# ProProject___2024-10-02.net
KiCad netlist of a schematic drawn in EasyEDA Pro
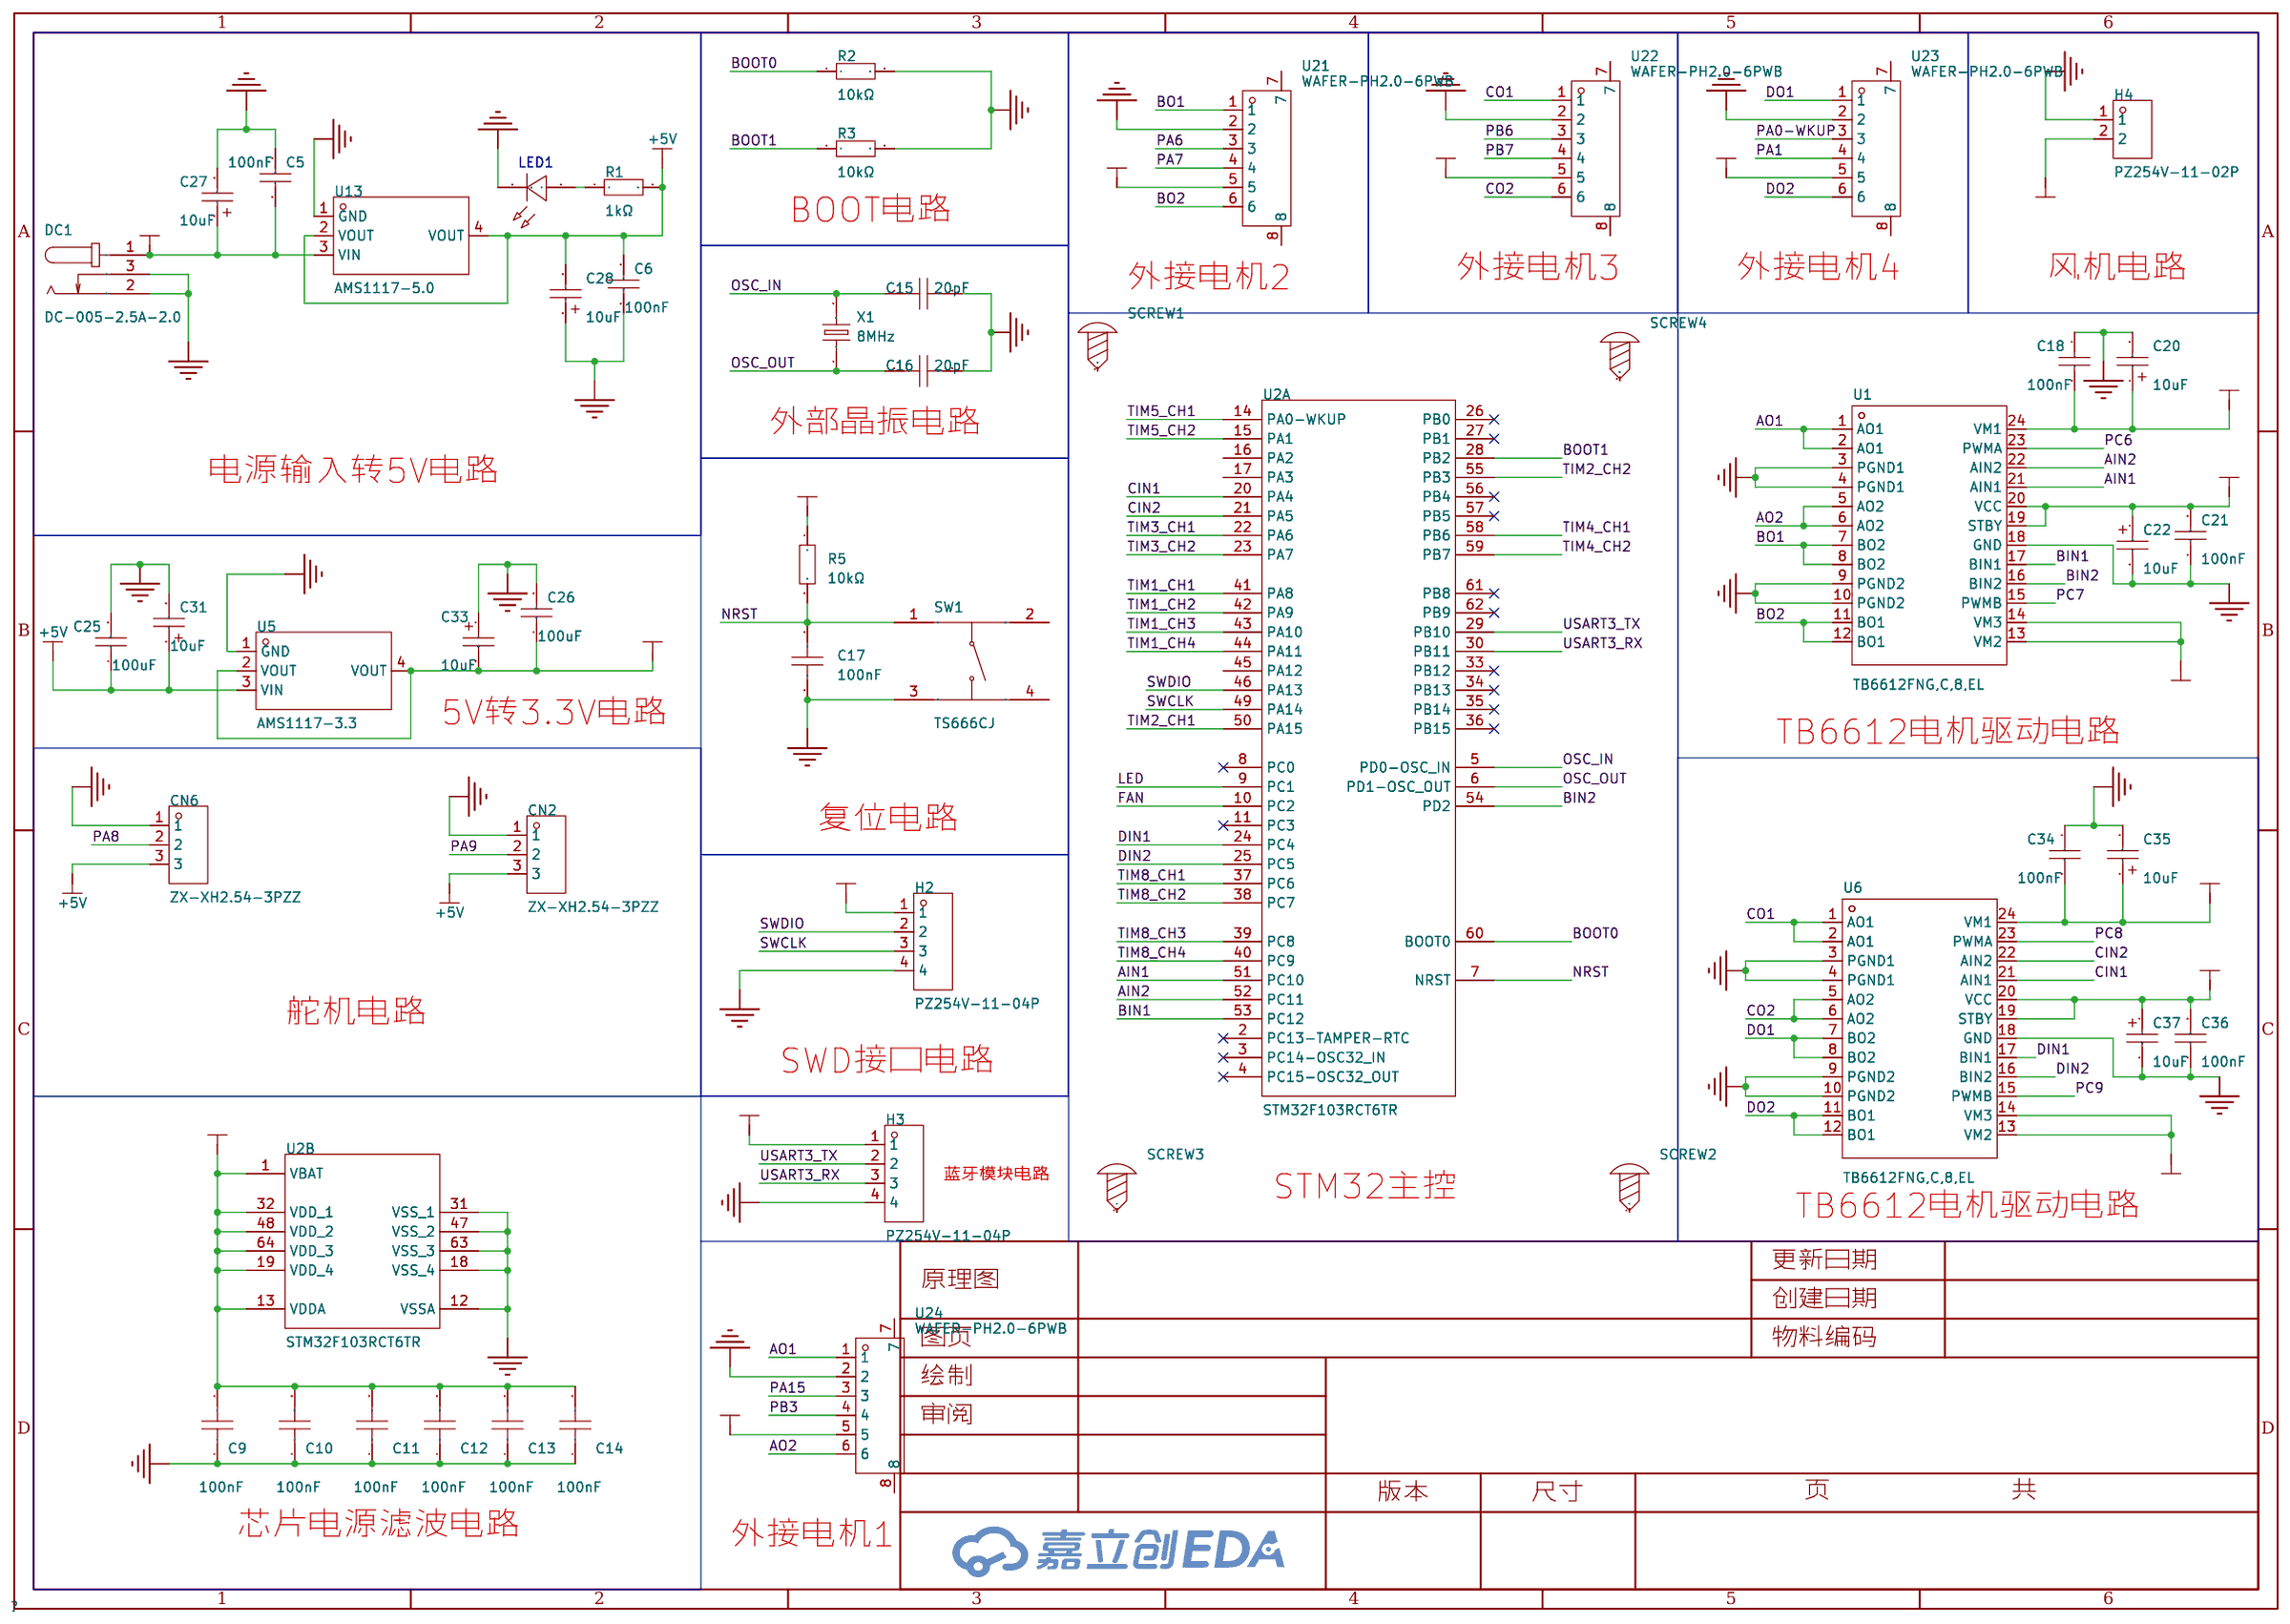
[diagram p0: schematic sheet]

(export (version "E")
  (design (tool "Eeschema 10.0.6"))
  (components
    (comp (ref "C5")
      (value "100nF")
      (footprint "easyedapro:C0805")
      (description "容值:100nF;精度:±10%;额定电压:50V;材质(温度系数):X7R;")
      (fields
        (field (name "Manufacturer Part") "CC0805KRX7R9BB104")
        (field (name "Manufacturer") "YAGEO(国巨)")
      )
      (libsource (lib "easyedapro") (part "CC0805KRX7R9BB104"))
    )
    (comp (ref "C6")
      (value "100nF")
      (footprint "easyedapro:C0805")
      (description "容值:100nF;精度:±10%;额定电压:50V;材质(温度系数):X7R;")
      (fields
        (field (name "Manufacturer Part") "CC0805KRX7R9BB104")
        (field (name "Manufacturer") "YAGEO(国巨)")
      )
      (libsource (lib "easyedapro") (part "CC0805KRX7R9BB104"))
    )
    (comp (ref "C9")
      (value "100nF")
      (footprint "easyedapro:C0603")
      (description "容值:100nF;精度:±10%;额定电压:50V;材质(温度系数):X7R;")
      (fields
        (field (name "Manufacturer Part") "CC0603KRX7R9BB104")
        (field (name "Manufacturer") "YAGEO(国巨)")
      )
      (libsource (lib "easyedapro") (part "CC0603KRX7R9BB104"))
    )
    (comp (ref "C10")
      (value "100nF")
      (footprint "easyedapro:C0603")
      (description "容值:100nF;精度:±10%;额定电压:50V;材质(温度系数):X7R;")
      (fields
        (field (name "Manufacturer Part") "CC0603KRX7R9BB104")
        (field (name "Manufacturer") "YAGEO(国巨)")
      )
      (libsource (lib "easyedapro") (part "CC0603KRX7R9BB104"))
    )
    (comp (ref "C11")
      (value "100nF")
      (footprint "easyedapro:C0603")
      (description "容值:100nF;精度:±10%;额定电压:50V;材质(温度系数):X7R;")
      (fields
        (field (name "Manufacturer Part") "CC0603KRX7R9BB104")
        (field (name "Manufacturer") "YAGEO(国巨)")
      )
      (libsource (lib "easyedapro") (part "CC0603KRX7R9BB104"))
    )
    (comp (ref "C12")
      (value "100nF")
      (footprint "easyedapro:C0603")
      (description "容值:100nF;精度:±10%;额定电压:50V;材质(温度系数):X7R;")
      (fields
        (field (name "Manufacturer Part") "CC0603KRX7R9BB104")
        (field (name "Manufacturer") "YAGEO(国巨)")
      )
      (libsource (lib "easyedapro") (part "CC0603KRX7R9BB104"))
    )
    (comp (ref "C13")
      (value "100nF")
      (footprint "easyedapro:C0603")
      (description "容值:100nF;精度:±10%;额定电压:50V;材质(温度系数):X7R;")
      (fields
        (field (name "Manufacturer Part") "CC0603KRX7R9BB104")
        (field (name "Manufacturer") "YAGEO(国巨)")
      )
      (libsource (lib "easyedapro") (part "CC0603KRX7R9BB104"))
    )
    (comp (ref "C14")
      (value "100nF")
      (footprint "easyedapro:C0603")
      (description "容值:100nF;精度:±10%;额定电压:50V;材质(温度系数):X7R;")
      (fields
        (field (name "Manufacturer Part") "CC0603KRX7R9BB104")
        (field (name "Manufacturer") "YAGEO(国巨)")
      )
      (libsource (lib "easyedapro") (part "CC0603KRX7R9BB104"))
    )
    (comp (ref "C15")
      (value "20pF")
      (footprint "easyedapro:C0805")
      (description "容值:20pF;精度:±5%;额定电压:50V;材质(温度系数):C0G;")
      (fields (field (name "Manufacturer Part") "0805CG200J500NT") (field (name "Manufacturer") "FH(风华)"))
      (libsource (lib "easyedapro") (part "0805CG200J500NT"))
    )
    (comp (ref "C16")
      (value "20pF")
      (footprint "easyedapro:C0805")
      (description "容值:20pF;精度:±5%;额定电压:50V;材质(温度系数):C0G;")
      (fields (field (name "Manufacturer Part") "0805CG200J500NT") (field (name "Manufacturer") "FH(风华)"))
      (libsource (lib "easyedapro") (part "0805CG200J500NT"))
    )
    (comp (ref "C17")
      (value "100nF")
      (footprint "easyedapro:C0603")
      (description "容值:100nF;精度:±10%;额定电压:50V;材质(温度系数):X7R;")
      (fields
        (field (name "Manufacturer Part") "CC0603KRX7R9BB104")
        (field (name "Manufacturer") "YAGEO(国巨)")
      )
      (libsource (lib "easyedapro") (part "CC0603KRX7R9BB104"))
    )
    (comp (ref "C18")
      (value "100nF")
      (footprint "easyedapro:C0805")
      (description "容值:100nF;精度:±10%;额定电压:50V;材质(温度系数):X7R;")
      (fields
        (field (name "Manufacturer Part") "CC0805KRX7R9BB104")
        (field (name "Manufacturer") "YAGEO(国巨)")
      )
      (libsource (lib "easyedapro") (part "CC0805KRX7R9BB104"))
    )
    (comp (ref "C20")
      (value "10uF")
      (footprint "easyedapro:CAP-SMD_L3.2-W1.6-RD-C7171")
      (description "容值:10uF;精度:±10%;额定电压:16V;等效串联电阻:3Ω@100kHz;")
      (fields (field (name "Manufacturer Part") "TAJA106K016RNJ") (field (name "Manufacturer") "Kyocera AVX"))
      (libsource (lib "easyedapro") (part "TAJA106K016RNJ"))
    )
    (comp (ref "C21")
      (value "100nF")
      (footprint "easyedapro:C0805")
      (description "容值:100nF;精度:±10%;额定电压:50V;材质(温度系数):X7R;")
      (fields
        (field (name "Manufacturer Part") "CC0805KRX7R9BB104")
        (field (name "Manufacturer") "YAGEO(国巨)")
      )
      (libsource (lib "easyedapro") (part "CC0805KRX7R9BB104"))
    )
    (comp (ref "C22")
      (value "10uF")
      (footprint "easyedapro:CAP-SMD_L3.2-W1.6-RD-C7171")
      (description "容值:10uF;精度:±10%;额定电压:16V;等效串联电阻:3Ω@100kHz;")
      (fields (field (name "Manufacturer Part") "TAJA106K016RNJ") (field (name "Manufacturer") "Kyocera AVX"))
      (libsource (lib "easyedapro") (part "TAJA106K016RNJ"))
    )
    (comp (ref "C25")
      (value "100uF")
      (footprint "easyedapro:C0805")
      (description "容值:100uF;精度:±20%;额定电压:6.3V;材质(温度系数):X5R;")
      (fields
        (field (name "Manufacturer Part") "GRM21BR60J107ME15L")
        (field (name "Manufacturer") "muRata(村田)")
      )
      (libsource (lib "easyedapro") (part "GRM21BR60J107ME15L"))
    )
    (comp (ref "C26")
      (value "100uF")
      (footprint "easyedapro:C0805")
      (description "容值:100uF;精度:±20%;额定电压:6.3V;材质(温度系数):X5R;")
      (fields
        (field (name "Manufacturer Part") "GRM21BR60J107ME15L")
        (field (name "Manufacturer") "muRata(村田)")
      )
      (libsource (lib "easyedapro") (part "GRM21BR60J107ME15L"))
    )
    (comp (ref "C27")
      (value "10uF")
      (footprint "easyedapro:CAP-SMD_L3.2-W1.6-RD-C7171")
      (description "容值:10uF;精度:±10%;额定电压:16V;等效串联电阻:3Ω@100kHz;")
      (fields (field (name "Manufacturer Part") "TAJA106K016RNJ") (field (name "Manufacturer") "Kyocera AVX"))
      (libsource (lib "easyedapro") (part "TAJA106K016RNJ"))
    )
    (comp (ref "C28")
      (value "10uF")
      (footprint "easyedapro:CAP-SMD_L3.2-W1.6-RD-C7171")
      (description "容值:10uF;精度:±10%;额定电压:16V;等效串联电阻:3Ω@100kHz;")
      (fields (field (name "Manufacturer Part") "TAJA106K016RNJ") (field (name "Manufacturer") "Kyocera AVX"))
      (libsource (lib "easyedapro") (part "TAJA106K016RNJ"))
    )
    (comp (ref "C31")
      (value "10uF")
      (footprint "easyedapro:CAP-SMD_L3.2-W1.6-RD-C7171")
      (description "容值:10uF;精度:±10%;额定电压:16V;等效串联电阻:3Ω@100kHz;")
      (fields (field (name "Manufacturer Part") "TAJA106K016RNJ") (field (name "Manufacturer") "Kyocera AVX"))
      (libsource (lib "easyedapro") (part "TAJA106K016RNJ"))
    )
    (comp (ref "C33")
      (value "10uF")
      (footprint "easyedapro:CAP-SMD_L3.2-W1.6-RD-C7171")
      (description "容值:10uF;精度:±10%;额定电压:16V;等效串联电阻:3Ω@100kHz;")
      (fields (field (name "Manufacturer Part") "TAJA106K016RNJ") (field (name "Manufacturer") "Kyocera AVX"))
      (libsource (lib "easyedapro") (part "TAJA106K016RNJ"))
    )
    (comp (ref "C34")
      (value "100nF")
      (footprint "easyedapro:C0805")
      (description "容值:100nF;精度:±10%;额定电压:50V;材质(温度系数):X7R;")
      (fields
        (field (name "Manufacturer Part") "CC0805KRX7R9BB104")
        (field (name "Manufacturer") "YAGEO(国巨)")
      )
      (libsource (lib "easyedapro") (part "CC0805KRX7R9BB104"))
    )
    (comp (ref "C35")
      (value "10uF")
      (footprint "easyedapro:CAP-SMD_L3.2-W1.6-RD-C7171")
      (description "容值:10uF;精度:±10%;额定电压:16V;等效串联电阻:3Ω@100kHz;")
      (fields (field (name "Manufacturer Part") "TAJA106K016RNJ") (field (name "Manufacturer") "Kyocera AVX"))
      (libsource (lib "easyedapro") (part "TAJA106K016RNJ"))
    )
    (comp (ref "C36")
      (value "100nF")
      (footprint "easyedapro:C0805")
      (description "容值:100nF;精度:±10%;额定电压:50V;材质(温度系数):X7R;")
      (fields
        (field (name "Manufacturer Part") "CC0805KRX7R9BB104")
        (field (name "Manufacturer") "YAGEO(国巨)")
      )
      (libsource (lib "easyedapro") (part "CC0805KRX7R9BB104"))
    )
    (comp (ref "C37")
      (value "10uF")
      (footprint "easyedapro:CAP-SMD_L3.2-W1.6-RD-C7171")
      (description "容值:10uF;精度:±10%;额定电压:16V;等效串联电阻:3Ω@100kHz;")
      (fields (field (name "Manufacturer Part") "TAJA106K016RNJ") (field (name "Manufacturer") "Kyocera AVX"))
      (libsource (lib "easyedapro") (part "TAJA106K016RNJ"))
    )
    (comp (ref "CN2")
      (value "ZX-XH2.54-3PZZ")
      (footprint "easyedapro:CONN-TH_3P-P2.54_2501S-3P")
      (fields (field (name "Manufacturer") "Megastar(兆星)"))
      (libsource (lib "easyedapro") (part "ZX-XH2.54-3PZZ"))
    )
    (comp (ref "CN6")
      (value "ZX-XH2.54-3PZZ")
      (footprint "easyedapro:CONN-TH_3P-P2.54_2501S-3P")
      (fields (field (name "Manufacturer") "Megastar(兆星)"))
      (libsource (lib "easyedapro") (part "ZX-XH2.54-3PZZ"))
    )
    (comp (ref "DC1")
      (value "DC-005-2.5A-2.0")
      (footprint "easyedapro:CONN-TH_DC-005-2.5A-2.0")
      (fields (field (name "Manufacturer") "XKB Connection(中国星坤)"))
      (libsource (lib "easyedapro") (part "DC-005-2.5A-2.0"))
    )
    (comp (ref "H2")
      (value "PZ254V-11-04P")
      (footprint "easyedapro:HDR-TH_4P-P2.54-V-M")
      (fields (field (name "Manufacturer") "XFCN(兴飞)"))
      (libsource (lib "easyedapro") (part "PZ254V-11-04P_C2691448"))
    )
    (comp (ref "H3")
      (value "PZ254V-11-04P")
      (footprint "easyedapro:HDR-TH_4P-P2.54-V-M")
      (fields (field (name "Manufacturer") "XFCN(兴飞)"))
      (libsource (lib "easyedapro") (part "PZ254V-11-04P_C2691448"))
    )
    (comp (ref "H4")
      (value "PZ254V-11-02P")
      (footprint "easyedapro:HDR-TH_2P-P2.54-V-M")
      (fields (field (name "Manufacturer") "XFCN(兴飞)"))
      (libsource (lib "easyedapro") (part "PZ254V-11-02P"))
    )
    (comp (ref "LED1")
      (value "~")
      (footprint "easyedapro:LED_0805")
      (libsource (lib "easyedapro") (part "LED_B"))
    )
    (comp (ref "R1")
      (value "1kΩ")
      (footprint "easyedapro:R0805")
      (description "电阻类型:厚膜电阻;阻值:1kΩ;精度:±1%;功率:125mW;最大工作电压:150V;温度系数:±100ppm/°C;")
      (fields
        (field (name "Manufacturer Part") "0805W8F1001T5E")
        (field (name "Manufacturer") "UNI-ROYAL(厚声)")
      )
      (libsource (lib "easyedapro") (part "0805W8F1001T5E"))
    )
    (comp (ref "R2")
      (value "10kΩ")
      (footprint "easyedapro:R0603")
      (description "电阻类型:厚膜电阻;阻值:10kΩ;精度:±1%;功率:100mW;最大工作电压:75V;温度系数:±100ppm/°C;")
      (fields
        (field (name "Manufacturer Part") "0603WAF1002T5E")
        (field (name "Manufacturer") "UNI-ROYAL(厚声)")
      )
      (libsource (lib "easyedapro") (part "0603WAF1002T5E"))
    )
    (comp (ref "R3")
      (value "10kΩ")
      (footprint "easyedapro:R0603")
      (description "电阻类型:厚膜电阻;阻值:10kΩ;精度:±1%;功率:100mW;最大工作电压:75V;温度系数:±100ppm/°C;")
      (fields
        (field (name "Manufacturer Part") "0603WAF1002T5E")
        (field (name "Manufacturer") "UNI-ROYAL(厚声)")
      )
      (libsource (lib "easyedapro") (part "0603WAF1002T5E"))
    )
    (comp (ref "R5")
      (value "10kΩ")
      (footprint "easyedapro:R0603")
      (description "电阻类型:厚膜电阻;阻值:10kΩ;精度:±1%;功率:100mW;最大工作电压:75V;温度系数:±100ppm/°C;")
      (fields
        (field (name "Manufacturer Part") "0603WAF1002T5E")
        (field (name "Manufacturer") "UNI-ROYAL(厚声)")
      )
      (libsource (lib "easyedapro") (part "0603WAF1002T5E"))
    )
    (comp (ref "SCREW1")
      (value "~")
      (footprint "easyedapro:M3螺丝")
      (libsource (lib "easyedapro") (part "螺丝孔"))
    )
    (comp (ref "SCREW2")
      (value "~")
      (footprint "easyedapro:M3螺丝")
      (libsource (lib "easyedapro") (part "螺丝孔"))
    )
    (comp (ref "SCREW3")
      (value "~")
      (footprint "easyedapro:M3螺丝")
      (libsource (lib "easyedapro") (part "螺丝孔"))
    )
    (comp (ref "SCREW4")
      (value "~")
      (footprint "easyedapro:M3螺丝")
      (libsource (lib "easyedapro") (part "螺丝孔"))
    )
    (comp (ref "SW1")
      (value "TS666CJ")
      (footprint "easyedapro:SW-TH_4P-L6.0-W6.0-P4.50-LS6.5")
      (fields (field (name "Manufacturer") "SHOU HAN(首韩)"))
      (libsource (lib "easyedapro") (part "TS666CJ"))
    )
    (comp (ref "U1")
      (value "TB6612FNG,C,8,EL")
      (footprint "easyedapro:SSOP-24_L8.3-W5.6-P0.65-LS7.6-BL")
      (fields (field (name "Manufacturer") "TOSHIBA(东芝)"))
      (libsource (lib "easyedapro") (part "TB6612FNG,C,8,EL"))
    )
    (comp (ref "U2")
      (value "STM32F103RCT6TR")
      (footprint "easyedapro:LQFP-64_L10.0-W10.0-P0.50-LS12.0-BL")
      (description "CPU内核:ARM-M3;程序存储容量:256KB;RAM总容量:48KB;GPIO端口数量:51;工作电压范围:2V~3.6V;CPU最大主频:72MHz;程序存储器类型:FLASH;")
      (fields (field (name "Manufacturer") "ST(意法半导体)"))
      (libsource (lib "easyedapro") (part "STM32F103RCT6TR"))
    )
    (comp (ref "U5")
      (value "AMS1117-3.3")
      (footprint "easyedapro:SOT-223-3_L6.5-W3.4-P2.30-LS7.0-BR")
      (description "输出类型:固定;最大输入电压:-;输出电压:3.3V;最大输出电流:1A;电源纹波抑制比(PSRR):72dB@(120Hz);输出极性:正极;")
      (fields (field (name "Manufacturer") "AMS"))
      (libsource (lib "easyedapro") (part "AMS1117-3.3"))
    )
    (comp (ref "U6")
      (value "TB6612FNG,C,8,EL")
      (footprint "easyedapro:SSOP-24_L8.3-W5.6-P0.65-LS7.6-BL")
      (fields (field (name "Manufacturer") "TOSHIBA(东芝)"))
      (libsource (lib "easyedapro") (part "TB6612FNG,C,8,EL"))
    )
    (comp (ref "U13")
      (value "AMS1117-5.0")
      (footprint "easyedapro:SOT-223_L6.5-W3.5-P2.30-LS7.0-BR")
      (description "输出类型:固定;最大输入电压:12V;输出电压:5V;最大输出电流:1A;电源纹波抑制比(PSRR):68dB@(120Hz);输出极性:正极;")
      (fields (field (name "Manufacturer") "AMS"))
      (libsource (lib "easyedapro") (part "AMS1117-5.0"))
    )
    (comp (ref "U21")
      (value "WAFER-PH2.0-6PWB")
      (footprint "easyedapro:CONN-SMD_6P-P2.00_XUNPU_WAFER-PH2.0-6PWB")
      (description "插针结构:1x6P;间距:2mm;安装方式:卧贴;总PIN数:6P;排数:1;每排PIN数:6;额定电流:2A;工作温度范围:-25°C~+85°C;")
      (fields (field (name "Manufacturer") "XUNPU(讯普)"))
      (libsource (lib "easyedapro") (part "WAFER-PH2.0-6PWB"))
    )
    (comp (ref "U22")
      (value "WAFER-PH2.0-6PWB")
      (footprint "easyedapro:CONN-SMD_6P-P2.00_XUNPU_WAFER-PH2.0-6PWB")
      (description "插针结构:1x6P;间距:2mm;安装方式:卧贴;总PIN数:6P;排数:1;每排PIN数:6;额定电流:2A;工作温度范围:-25°C~+85°C;")
      (fields (field (name "Manufacturer") "XUNPU(讯普)"))
      (libsource (lib "easyedapro") (part "WAFER-PH2.0-6PWB"))
    )
    (comp (ref "U23")
      (value "WAFER-PH2.0-6PWB")
      (footprint "easyedapro:CONN-SMD_6P-P2.00_XUNPU_WAFER-PH2.0-6PWB")
      (description "插针结构:1x6P;间距:2mm;安装方式:卧贴;总PIN数:6P;排数:1;每排PIN数:6;额定电流:2A;工作温度范围:-25°C~+85°C;")
      (fields (field (name "Manufacturer") "XUNPU(讯普)"))
      (libsource (lib "easyedapro") (part "WAFER-PH2.0-6PWB"))
    )
    (comp (ref "U24")
      (value "WAFER-PH2.0-6PWB")
      (footprint "easyedapro:CONN-SMD_6P-P2.00_XUNPU_WAFER-PH2.0-6PWB")
      (description "插针结构:1x6P;间距:2mm;安装方式:卧贴;总PIN数:6P;排数:1;每排PIN数:6;额定电流:2A;工作温度范围:-25°C~+85°C;")
      (fields (field (name "Manufacturer") "XUNPU(讯普)"))
      (libsource (lib "easyedapro") (part "WAFER-PH2.0-6PWB"))
    )
    (comp (ref "X1")
      (value "8MHz")
      (footprint "easyedapro:HC-49US_L11.5-W4.5-P4.88")
      (description "晶振类型:直插晶振;频率:8MHz;常温频差:±20ppm;外接负载电容:20pF;频率稳定度(全温):±20ppm;")
      (fields
        (field (name "Manufacturer Part") "49S-8.000-20-20-20/A")
        (field (name "Manufacturer") "LIMING(利明)")
      )
      (libsource (lib "easyedapro") (part "49S-8.000-20-20-20/A"))
    )
  )
  (nets
    (net (code "1") (name "+3.3V") (class "Default")
      (node (ref "C10") (pin "2") (pinfunction "2_2") (pintype "unspecified"))
      (node (ref "C11") (pin "2") (pinfunction "2_2") (pintype "unspecified"))
      (node (ref "C12") (pin "2") (pinfunction "2_2") (pintype "unspecified"))
      (node (ref "C13") (pin "2") (pinfunction "2_2") (pintype "unspecified"))
      (node (ref "C14") (pin "2") (pinfunction "2_2") (pintype "unspecified"))
      (node (ref "C21") (pin "2") (pinfunction "2_2") (pintype "input"))
      (node (ref "C22") (pin "1") (pinfunction "1_1") (pintype "input"))
      (node (ref "C26") (pin "1") (pinfunction "1_1") (pintype "input"))
      (node (ref "C33") (pin "2") (pinfunction "2_2") (pintype "input"))
      (node (ref "C36") (pin "2") (pinfunction "2_2") (pintype "input"))
      (node (ref "C37") (pin "1") (pinfunction "1_1") (pintype "input"))
      (node (ref "C9") (pin "2") (pinfunction "2_2") (pintype "unspecified"))
      (node (ref "H2") (pin "1") (pinfunction "1_1") (pintype "unspecified"))
      (node (ref "H3") (pin "1") (pinfunction "1_1") (pintype "unspecified"))
      (node (ref "R5") (pin "1") (pinfunction "1_1") (pintype "input"))
      (node (ref "U1") (pin "19") (pinfunction "STBY_19") (pintype "unspecified"))
      (node (ref "U1") (pin "20") (pinfunction "VCC_20") (pintype "unspecified"))
      (node (ref "U2") (pin "1") (pinfunction "VBAT_1") (pintype "unspecified"))
      (node (ref "U2") (pin "13") (pinfunction "VDDA_13") (pintype "unspecified"))
      (node (ref "U2") (pin "19") (pinfunction "VDD_4_19") (pintype "unspecified"))
      (node (ref "U2") (pin "32") (pinfunction "VDD_1_32") (pintype "unspecified"))
      (node (ref "U2") (pin "48") (pinfunction "VDD_2_48") (pintype "unspecified"))
      (node (ref "U2") (pin "64") (pinfunction "VDD_3_64") (pintype "unspecified"))
      (node (ref "U21") (pin "5") (pinfunction "5_5") (pintype "unspecified"))
      (node (ref "U22") (pin "5") (pinfunction "5_5") (pintype "unspecified"))
      (node (ref "U23") (pin "5") (pinfunction "5_5") (pintype "unspecified"))
      (node (ref "U24") (pin "5") (pinfunction "5_5") (pintype "unspecified"))
      (node (ref "U5") (pin "2") (pinfunction "VOUT_2") (pintype "unspecified"))
      (node (ref "U5") (pin "4") (pinfunction "VOUT_4") (pintype "unspecified"))
      (node (ref "U6") (pin "19") (pinfunction "STBY_19") (pintype "unspecified"))
      (node (ref "U6") (pin "20") (pinfunction "VCC_20") (pintype "unspecified"))
    )
    (net (code "2") (name "+5V") (class "Default")
      (node (ref "C25") (pin "1") (pinfunction "1_1") (pintype "input"))
      (node (ref "C28") (pin "2") (pinfunction "2_2") (pintype "input"))
      (node (ref "C31") (pin "1") (pinfunction "1_1") (pintype "input"))
      (node (ref "C6") (pin "1") (pinfunction "1_1") (pintype "input"))
      (node (ref "CN2") (pin "3") (pinfunction "3_3") (pintype "unspecified"))
      (node (ref "CN6") (pin "3") (pinfunction "3_3") (pintype "unspecified"))
      (node (ref "R1") (pin "2") (pinfunction "2_2") (pintype "input"))
      (node (ref "U13") (pin "2") (pinfunction "VOUT_2") (pintype "unspecified"))
      (node (ref "U13") (pin "4") (pinfunction "VOUT_4") (pintype "unspecified"))
      (node (ref "U5") (pin "3") (pinfunction "VIN_3") (pintype "unspecified"))
    )
    (net (code "3") (name "+12V") (class "Default")
      (node (ref "C18") (pin "2") (pinfunction "2_2") (pintype "input"))
      (node (ref "C20") (pin "1") (pinfunction "1_1") (pintype "input"))
      (node (ref "C27") (pin "1") (pinfunction "1_1") (pintype "input"))
      (node (ref "C34") (pin "2") (pinfunction "2_2") (pintype "input"))
      (node (ref "C35") (pin "1") (pinfunction "1_1") (pintype "input"))
      (node (ref "C5") (pin "2") (pinfunction "2_2") (pintype "input"))
      (node (ref "DC1") (pin "1") (pinfunction "1_1") (pintype "unspecified"))
      (node (ref "H4") (pin "2") (pinfunction "2_2") (pintype "unspecified"))
      (node (ref "U1") (pin "13") (pinfunction "VM2_13") (pintype "unspecified"))
      (node (ref "U1") (pin "14") (pinfunction "VM3_14") (pintype "unspecified"))
      (node (ref "U1") (pin "24") (pinfunction "VM1_24") (pintype "unspecified"))
      (node (ref "U13") (pin "3") (pinfunction "VIN_3") (pintype "unspecified"))
      (node (ref "U6") (pin "13") (pinfunction "VM2_13") (pintype "unspecified"))
      (node (ref "U6") (pin "14") (pinfunction "VM3_14") (pintype "unspecified"))
      (node (ref "U6") (pin "24") (pinfunction "VM1_24") (pintype "unspecified"))
    )
    (net (code "4") (name "/AIN1") (class "Default")
      (node (ref "U1") (pin "21") (pinfunction "AIN1_21") (pintype "unspecified"))
      (node (ref "U2") (pin "51") (pinfunction "PC10_51") (pintype "bidirectional"))
    )
    (net (code "5") (name "/AIN2") (class "Default")
      (node (ref "U1") (pin "22") (pinfunction "AIN2_22") (pintype "unspecified"))
      (node (ref "U2") (pin "52") (pinfunction "PC11_52") (pintype "bidirectional"))
    )
    (net (code "6") (name "/AO1") (class "Default")
      (node (ref "U1") (pin "1") (pinfunction "AO1_1") (pintype "unspecified"))
      (node (ref "U1") (pin "2") (pinfunction "AO1_2") (pintype "unspecified"))
      (node (ref "U24") (pin "1") (pinfunction "1_1") (pintype "unspecified"))
    )
    (net (code "7") (name "/AO2") (class "Default")
      (node (ref "U1") (pin "5") (pinfunction "AO2_5") (pintype "unspecified"))
      (node (ref "U1") (pin "6") (pinfunction "AO2_6") (pintype "unspecified"))
      (node (ref "U24") (pin "6") (pinfunction "6_6") (pintype "unspecified"))
    )
    (net (code "8") (name "/BIN1") (class "Default")
      (node (ref "U1") (pin "17") (pinfunction "BIN1_17") (pintype "unspecified"))
      (node (ref "U2") (pin "53") (pinfunction "PC12_53") (pintype "bidirectional"))
    )
    (net (code "9") (name "/BIN2") (class "Default")
      (node (ref "U1") (pin "16") (pinfunction "BIN2_16") (pintype "unspecified"))
      (node (ref "U2") (pin "54") (pinfunction "PD2_54") (pintype "bidirectional"))
    )
    (net (code "10") (name "/BO1") (class "Default")
      (node (ref "U1") (pin "7") (pinfunction "BO2_7") (pintype "unspecified"))
      (node (ref "U1") (pin "8") (pinfunction "BO2_8") (pintype "unspecified"))
      (node (ref "U21") (pin "1") (pinfunction "1_1") (pintype "unspecified"))
    )
    (net (code "11") (name "/BO2") (class "Default")
      (node (ref "U1") (pin "11") (pinfunction "BO1_11") (pintype "unspecified"))
      (node (ref "U1") (pin "12") (pinfunction "BO1_12") (pintype "unspecified"))
      (node (ref "U21") (pin "6") (pinfunction "6_6") (pintype "unspecified"))
    )
    (net (code "12") (name "/BOOT0") (class "Default")
      (node (ref "R2") (pin "1") (pinfunction "1_1") (pintype "input"))
      (node (ref "U2") (pin "60") (pinfunction "BOOT0_60") (pintype "unspecified"))
    )
    (net (code "13") (name "/BOOT1") (class "Default")
      (node (ref "R3") (pin "1") (pinfunction "1_1") (pintype "input"))
      (node (ref "U2") (pin "28") (pinfunction "PB2_28") (pintype "bidirectional"))
    )
    (net (code "14") (name "/CIN1") (class "Default")
      (node (ref "U2") (pin "20") (pinfunction "PA4_20") (pintype "bidirectional"))
      (node (ref "U6") (pin "21") (pinfunction "AIN1_21") (pintype "unspecified"))
    )
    (net (code "15") (name "/CIN2") (class "Default")
      (node (ref "U2") (pin "21") (pinfunction "PA5_21") (pintype "bidirectional"))
      (node (ref "U6") (pin "22") (pinfunction "AIN2_22") (pintype "unspecified"))
    )
    (net (code "16") (name "/CO1") (class "Default")
      (node (ref "U22") (pin "1") (pinfunction "1_1") (pintype "unspecified"))
      (node (ref "U6") (pin "1") (pinfunction "AO1_1") (pintype "unspecified"))
      (node (ref "U6") (pin "2") (pinfunction "AO1_2") (pintype "unspecified"))
    )
    (net (code "17") (name "/CO2") (class "Default")
      (node (ref "U22") (pin "6") (pinfunction "6_6") (pintype "unspecified"))
      (node (ref "U6") (pin "5") (pinfunction "AO2_5") (pintype "unspecified"))
      (node (ref "U6") (pin "6") (pinfunction "AO2_6") (pintype "unspecified"))
    )
    (net (code "18") (name "/DIN1") (class "Default")
      (node (ref "U2") (pin "24") (pinfunction "PC4_24") (pintype "bidirectional"))
      (node (ref "U6") (pin "17") (pinfunction "BIN1_17") (pintype "unspecified"))
    )
    (net (code "19") (name "/DIN2") (class "Default")
      (node (ref "U2") (pin "25") (pinfunction "PC5_25") (pintype "bidirectional"))
      (node (ref "U6") (pin "16") (pinfunction "BIN2_16") (pintype "unspecified"))
    )
    (net (code "20") (name "/DO1") (class "Default")
      (node (ref "U23") (pin "1") (pinfunction "1_1") (pintype "unspecified"))
      (node (ref "U6") (pin "7") (pinfunction "BO2_7") (pintype "unspecified"))
      (node (ref "U6") (pin "8") (pinfunction "BO2_8") (pintype "unspecified"))
    )
    (net (code "21") (name "/DO2") (class "Default")
      (node (ref "U23") (pin "6") (pinfunction "6_6") (pintype "unspecified"))
      (node (ref "U6") (pin "11") (pinfunction "BO1_11") (pintype "unspecified"))
      (node (ref "U6") (pin "12") (pinfunction "BO1_12") (pintype "unspecified"))
    )
    (net (code "22") (name "/FAN") (class "Default")
      (node (ref "U2") (pin "10") (pinfunction "PC2_10") (pintype "bidirectional"))
    )
    (net (code "23") (name "/LED") (class "Default")
      (node (ref "U2") (pin "9") (pinfunction "PC1_9") (pintype "bidirectional"))
    )
    (net (code "24") (name "/NRST") (class "Default")
      (node (ref "C17") (pin "2") (pinfunction "2_2") (pintype "unspecified"))
      (node (ref "R5") (pin "2") (pinfunction "2_2") (pintype "input"))
      (node (ref "SW1") (pin "1") (pinfunction "A_1") (pintype "input"))
      (node (ref "U2") (pin "7") (pinfunction "NRST_7") (pintype "bidirectional"))
    )
    (net (code "25") (name "/OSC_IN") (class "Default")
      (node (ref "C15") (pin "1") (pinfunction "1_1") (pintype "unspecified"))
      (node (ref "U2") (pin "5") (pinfunction "PD0-OSC_IN_5") (pintype "bidirectional"))
      (node (ref "X1") (pin "2") (pinfunction "2_2") (pintype "input"))
    )
    (net (code "26") (name "/OSC_OUT") (class "Default")
      (node (ref "C16") (pin "1") (pinfunction "1_1") (pintype "unspecified"))
      (node (ref "U2") (pin "6") (pinfunction "PD1-OSC_OUT_6") (pintype "bidirectional"))
      (node (ref "X1") (pin "1") (pinfunction "1_1") (pintype "input"))
    )
    (net (code "27") (name "/PA0-WKUP") (class "Default")
      (node (ref "U23") (pin "3") (pinfunction "3_3") (pintype "unspecified"))
    )
    (net (code "28") (name "/PA1") (class "Default")
      (node (ref "U23") (pin "4") (pinfunction "4_4") (pintype "unspecified"))
    )
    (net (code "29") (name "/PA6") (class "Default")
      (node (ref "U21") (pin "3") (pinfunction "3_3") (pintype "unspecified"))
    )
    (net (code "30") (name "/PA7") (class "Default")
      (node (ref "U21") (pin "4") (pinfunction "4_4") (pintype "unspecified"))
    )
    (net (code "31") (name "/PA8") (class "Default")
      (node (ref "CN6") (pin "2") (pinfunction "2_2") (pintype "unspecified"))
    )
    (net (code "32") (name "/PA9") (class "Default")
      (node (ref "CN2") (pin "2") (pinfunction "2_2") (pintype "unspecified"))
    )
    (net (code "33") (name "/PA15") (class "Default")
      (node (ref "U24") (pin "3") (pinfunction "3_3") (pintype "unspecified"))
    )
    (net (code "34") (name "/PB3") (class "Default")
      (node (ref "U24") (pin "4") (pinfunction "4_4") (pintype "unspecified"))
    )
    (net (code "35") (name "/PB6") (class "Default")
      (node (ref "U22") (pin "3") (pinfunction "3_3") (pintype "unspecified"))
    )
    (net (code "36") (name "/PB7") (class "Default")
      (node (ref "U22") (pin "4") (pinfunction "4_4") (pintype "unspecified"))
    )
    (net (code "37") (name "/PC6") (class "Default")
      (node (ref "U1") (pin "23") (pinfunction "PWMA_23") (pintype "unspecified"))
    )
    (net (code "38") (name "/PC7") (class "Default")
      (node (ref "U1") (pin "15") (pinfunction "PWMB_15") (pintype "unspecified"))
    )
    (net (code "39") (name "/PC8") (class "Default")
      (node (ref "U6") (pin "23") (pinfunction "PWMA_23") (pintype "unspecified"))
    )
    (net (code "40") (name "/PC9") (class "Default")
      (node (ref "U6") (pin "15") (pinfunction "PWMB_15") (pintype "unspecified"))
    )
    (net (code "41") (name "/SWCLK") (class "Default")
      (node (ref "H2") (pin "3") (pinfunction "3_3") (pintype "unspecified"))
      (node (ref "U2") (pin "49") (pinfunction "PA14_49") (pintype "bidirectional"))
    )
    (net (code "42") (name "/SWDIO") (class "Default")
      (node (ref "H2") (pin "2") (pinfunction "2_2") (pintype "unspecified"))
      (node (ref "U2") (pin "46") (pinfunction "PA13_46") (pintype "bidirectional"))
    )
    (net (code "43") (name "/TIM1_CH1") (class "Default")
      (node (ref "U2") (pin "41") (pinfunction "PA8_41") (pintype "bidirectional"))
    )
    (net (code "44") (name "/TIM1_CH2") (class "Default")
      (node (ref "U2") (pin "42") (pinfunction "PA9_42") (pintype "bidirectional"))
    )
    (net (code "45") (name "/TIM1_CH3") (class "Default")
      (node (ref "U2") (pin "43") (pinfunction "PA10_43") (pintype "bidirectional"))
    )
    (net (code "46") (name "/TIM1_CH4") (class "Default")
      (node (ref "U2") (pin "44") (pinfunction "PA11_44") (pintype "bidirectional"))
    )
    (net (code "47") (name "/TIM2_CH1") (class "Default")
      (node (ref "U2") (pin "50") (pinfunction "PA15_50") (pintype "bidirectional"))
    )
    (net (code "48") (name "/TIM2_CH2") (class "Default")
      (node (ref "U2") (pin "55") (pinfunction "PB3_55") (pintype "bidirectional"))
    )
    (net (code "49") (name "/TIM3_CH1") (class "Default")
      (node (ref "U2") (pin "22") (pinfunction "PA6_22") (pintype "bidirectional"))
    )
    (net (code "50") (name "/TIM3_CH2") (class "Default")
      (node (ref "U2") (pin "23") (pinfunction "PA7_23") (pintype "bidirectional"))
    )
    (net (code "51") (name "/TIM4_CH1") (class "Default")
      (node (ref "U2") (pin "58") (pinfunction "PB6_58") (pintype "bidirectional"))
    )
    (net (code "52") (name "/TIM4_CH2") (class "Default")
      (node (ref "U2") (pin "59") (pinfunction "PB7_59") (pintype "bidirectional"))
    )
    (net (code "53") (name "/TIM5_CH1") (class "Default")
      (node (ref "U2") (pin "14") (pinfunction "PA0-WKUP_14") (pintype "bidirectional"))
    )
    (net (code "54") (name "/TIM5_CH2") (class "Default")
      (node (ref "U2") (pin "15") (pinfunction "PA1_15") (pintype "bidirectional"))
    )
    (net (code "55") (name "/TIM8_CH1") (class "Default")
      (node (ref "U2") (pin "37") (pinfunction "PC6_37") (pintype "bidirectional"))
    )
    (net (code "56") (name "/TIM8_CH2") (class "Default")
      (node (ref "U2") (pin "38") (pinfunction "PC7_38") (pintype "bidirectional"))
    )
    (net (code "57") (name "/TIM8_CH3") (class "Default")
      (node (ref "U2") (pin "39") (pinfunction "PC8_39") (pintype "bidirectional"))
    )
    (net (code "58") (name "/TIM8_CH4") (class "Default")
      (node (ref "U2") (pin "40") (pinfunction "PC9_40") (pintype "bidirectional"))
    )
    (net (code "59") (name "/USART3_RX") (class "Default")
      (node (ref "H3") (pin "3") (pinfunction "3_3") (pintype "unspecified"))
      (node (ref "U2") (pin "30") (pinfunction "PB11_30") (pintype "bidirectional"))
    )
    (net (code "60") (name "/USART3_TX") (class "Default")
      (node (ref "H3") (pin "2") (pinfunction "2_2") (pintype "unspecified"))
      (node (ref "U2") (pin "29") (pinfunction "PB10_29") (pintype "bidirectional"))
    )
    (net (code "61") (name "GND") (class "Default")
      (node (ref "C10") (pin "1") (pinfunction "1_1") (pintype "unspecified"))
      (node (ref "C11") (pin "1") (pinfunction "1_1") (pintype "unspecified"))
      (node (ref "C12") (pin "1") (pinfunction "1_1") (pintype "unspecified"))
      (node (ref "C13") (pin "1") (pinfunction "1_1") (pintype "unspecified"))
      (node (ref "C14") (pin "1") (pinfunction "1_1") (pintype "unspecified"))
      (node (ref "C15") (pin "2") (pinfunction "2_2") (pintype "unspecified"))
      (node (ref "C16") (pin "2") (pinfunction "2_2") (pintype "unspecified"))
      (node (ref "C17") (pin "1") (pinfunction "1_1") (pintype "unspecified"))
      (node (ref "C18") (pin "1") (pinfunction "1_1") (pintype "input"))
      (node (ref "C20") (pin "2") (pinfunction "2_2") (pintype "input"))
      (node (ref "C21") (pin "1") (pinfunction "1_1") (pintype "input"))
      (node (ref "C22") (pin "2") (pinfunction "2_2") (pintype "input"))
      (node (ref "C25") (pin "2") (pinfunction "2_2") (pintype "input"))
      (node (ref "C26") (pin "2") (pinfunction "2_2") (pintype "input"))
      (node (ref "C27") (pin "2") (pinfunction "2_2") (pintype "input"))
      (node (ref "C28") (pin "1") (pinfunction "1_1") (pintype "input"))
      (node (ref "C31") (pin "2") (pinfunction "2_2") (pintype "input"))
      (node (ref "C33") (pin "1") (pinfunction "1_1") (pintype "input"))
      (node (ref "C34") (pin "1") (pinfunction "1_1") (pintype "input"))
      (node (ref "C35") (pin "2") (pinfunction "2_2") (pintype "input"))
      (node (ref "C36") (pin "1") (pinfunction "1_1") (pintype "input"))
      (node (ref "C37") (pin "2") (pinfunction "2_2") (pintype "input"))
      (node (ref "C5") (pin "1") (pinfunction "1_1") (pintype "input"))
      (node (ref "C6") (pin "2") (pinfunction "2_2") (pintype "input"))
      (node (ref "C9") (pin "1") (pinfunction "1_1") (pintype "unspecified"))
      (node (ref "CN2") (pin "1") (pinfunction "1_1") (pintype "unspecified"))
      (node (ref "CN6") (pin "1") (pinfunction "1_1") (pintype "unspecified"))
      (node (ref "DC1") (pin "2") (pinfunction "2_2") (pintype "unspecified"))
      (node (ref "DC1") (pin "3") (pinfunction "3_3") (pintype "unspecified"))
      (node (ref "H2") (pin "4") (pinfunction "4_4") (pintype "unspecified"))
      (node (ref "H3") (pin "4") (pinfunction "4_4") (pintype "unspecified"))
      (node (ref "H4") (pin "1") (pinfunction "1_1") (pintype "unspecified"))
      (node (ref "LED1") (pin "1") (pinfunction "C_1") (pintype "input"))
      (node (ref "R2") (pin "2") (pinfunction "2_2") (pintype "input"))
      (node (ref "R3") (pin "2") (pinfunction "2_2") (pintype "input"))
      (node (ref "SW1") (pin "3") (pinfunction "C_3") (pintype "input"))
      (node (ref "U1") (pin "10") (pinfunction "PGND2_10") (pintype "unspecified"))
      (node (ref "U1") (pin "18") (pinfunction "GND_18") (pintype "unspecified"))
      (node (ref "U1") (pin "3") (pinfunction "PGND1_3") (pintype "unspecified"))
      (node (ref "U1") (pin "4") (pinfunction "PGND1_4") (pintype "unspecified"))
      (node (ref "U1") (pin "9") (pinfunction "PGND2_9") (pintype "unspecified"))
      (node (ref "U13") (pin "1") (pinfunction "GND_1") (pintype "unspecified"))
      (node (ref "U2") (pin "12") (pinfunction "VSSA_12") (pintype "unspecified"))
      (node (ref "U2") (pin "18") (pinfunction "VSS_4_18") (pintype "unspecified"))
      (node (ref "U2") (pin "31") (pinfunction "VSS_1_31") (pintype "unspecified"))
      (node (ref "U2") (pin "47") (pinfunction "VSS_2_47") (pintype "unspecified"))
      (node (ref "U2") (pin "63") (pinfunction "VSS_3_63") (pintype "unspecified"))
      (node (ref "U21") (pin "2") (pinfunction "2_2") (pintype "unspecified"))
      (node (ref "U22") (pin "2") (pinfunction "2_2") (pintype "unspecified"))
      (node (ref "U23") (pin "2") (pinfunction "2_2") (pintype "unspecified"))
      (node (ref "U24") (pin "2") (pinfunction "2_2") (pintype "unspecified"))
      (node (ref "U5") (pin "1") (pinfunction "GND_1") (pintype "unspecified"))
      (node (ref "U6") (pin "10") (pinfunction "PGND2_10") (pintype "unspecified"))
      (node (ref "U6") (pin "18") (pinfunction "GND_18") (pintype "unspecified"))
      (node (ref "U6") (pin "3") (pinfunction "PGND1_3") (pintype "unspecified"))
      (node (ref "U6") (pin "4") (pinfunction "PGND1_4") (pintype "unspecified"))
      (node (ref "U6") (pin "9") (pinfunction "PGND2_9") (pintype "unspecified"))
    )
    (net (code "62") (name "Net-(LED1-A)") (class "Default")
      (node (ref "LED1") (pin "2") (pinfunction "A_2") (pintype "input"))
      (node (ref "R1") (pin "1") (pinfunction "1_1") (pintype "input"))
    )
    (net (code "63") (name "unconnected-(SCREW1-Pad1)") (class "Default")
      (node (ref "SCREW1") (pin "1") (pinfunction "1_1") (pintype "input"))
    )
    (net (code "64") (name "unconnected-(SCREW2-Pad1)") (class "Default")
      (node (ref "SCREW2") (pin "1") (pinfunction "1_1") (pintype "input"))
    )
    (net (code "65") (name "unconnected-(SCREW3-Pad1)") (class "Default")
      (node (ref "SCREW3") (pin "1") (pinfunction "1_1") (pintype "input"))
    )
    (net (code "66") (name "unconnected-(SCREW4-Pad1)") (class "Default")
      (node (ref "SCREW4") (pin "1") (pinfunction "1_1") (pintype "input"))
    )
    (net (code "67") (name "unconnected-(SW1-B-Pad2)") (class "Default")
      (node (ref "SW1") (pin "2") (pinfunction "B_2") (pintype "input"))
    )
    (net (code "68") (name "unconnected-(SW1-D-Pad4)") (class "Default")
      (node (ref "SW1") (pin "4") (pinfunction "D_4") (pintype "input"))
    )
    (net (code "69") (name "unconnected-(U2A-PA2-Pad16)") (class "Default")
      (node (ref "U2") (pin "16") (pinfunction "PA2_16") (pintype "bidirectional"))
    )
    (net (code "70") (name "unconnected-(U2A-PA3-Pad17)") (class "Default")
      (node (ref "U2") (pin "17") (pinfunction "PA3_17") (pintype "bidirectional"))
    )
    (net (code "71") (name "unconnected-(U2A-PA12-Pad45)") (class "Default")
      (node (ref "U2") (pin "45") (pinfunction "PA12_45") (pintype "bidirectional"))
    )
    (net (code "72") (name "unconnected-(U2A-PB0-Pad26)") (class "Default")
      (node (ref "U2") (pin "26") (pinfunction "PB0_26") (pintype "bidirectional+no_connect"))
    )
    (net (code "73") (name "unconnected-(U2A-PB1-Pad27)") (class "Default")
      (node (ref "U2") (pin "27") (pinfunction "PB1_27") (pintype "bidirectional+no_connect"))
    )
    (net (code "74") (name "unconnected-(U2A-PB4-Pad56)") (class "Default")
      (node (ref "U2") (pin "56") (pinfunction "PB4_56") (pintype "bidirectional+no_connect"))
    )
    (net (code "75") (name "unconnected-(U2A-PB5-Pad57)") (class "Default")
      (node (ref "U2") (pin "57") (pinfunction "PB5_57") (pintype "bidirectional+no_connect"))
    )
    (net (code "76") (name "unconnected-(U2A-PB8-Pad61)") (class "Default")
      (node (ref "U2") (pin "61") (pinfunction "PB8_61") (pintype "bidirectional+no_connect"))
    )
    (net (code "77") (name "unconnected-(U2A-PB9-Pad62)") (class "Default")
      (node (ref "U2") (pin "62") (pinfunction "PB9_62") (pintype "bidirectional+no_connect"))
    )
    (net (code "78") (name "unconnected-(U2A-PB12-Pad33)") (class "Default")
      (node (ref "U2") (pin "33") (pinfunction "PB12_33") (pintype "bidirectional+no_connect"))
    )
    (net (code "79") (name "unconnected-(U2A-PB13-Pad34)") (class "Default")
      (node (ref "U2") (pin "34") (pinfunction "PB13_34") (pintype "bidirectional+no_connect"))
    )
    (net (code "80") (name "unconnected-(U2A-PB14-Pad35)") (class "Default")
      (node (ref "U2") (pin "35") (pinfunction "PB14_35") (pintype "bidirectional+no_connect"))
    )
    (net (code "81") (name "unconnected-(U2A-PB15-Pad36)") (class "Default")
      (node (ref "U2") (pin "36") (pinfunction "PB15_36") (pintype "bidirectional+no_connect"))
    )
    (net (code "82") (name "unconnected-(U2A-PC0-Pad8)") (class "Default")
      (node (ref "U2") (pin "8") (pinfunction "PC0_8") (pintype "bidirectional+no_connect"))
    )
    (net (code "83") (name "unconnected-(U2A-PC3-Pad11)") (class "Default")
      (node (ref "U2") (pin "11") (pinfunction "PC3_11") (pintype "bidirectional+no_connect"))
    )
    (net (code "84") (name "unconnected-(U2A-PC13-TAMPER-RTC-Pad2)") (class "Default")
      (node (ref "U2") (pin "2") (pinfunction "PC13-TAMPER-RTC_2") (pintype "bidirectional+no_connect"))
    )
    (net (code "85") (name "unconnected-(U2A-PC14-OSC32_IN-Pad3)") (class "Default")
      (node (ref "U2") (pin "3") (pinfunction "PC14-OSC32_IN_3") (pintype "bidirectional+no_connect"))
    )
    (net (code "86") (name "unconnected-(U2A-PC15-OSC32_OUT-Pad4)") (class "Default")
      (node (ref "U2") (pin "4") (pinfunction "PC15-OSC32_OUT_4") (pintype "bidirectional+no_connect"))
    )
    (net (code "87") (name "unconnected-(U21-Pad7)") (class "Default")
      (node (ref "U21") (pin "7") (pinfunction "7_7") (pintype "unspecified"))
    )
    (net (code "88") (name "unconnected-(U21-Pad8)") (class "Default")
      (node (ref "U21") (pin "8") (pinfunction "8_8") (pintype "unspecified"))
    )
    (net (code "89") (name "unconnected-(U22-Pad7)") (class "Default")
      (node (ref "U22") (pin "7") (pinfunction "7_7") (pintype "unspecified"))
    )
    (net (code "90") (name "unconnected-(U22-Pad8)") (class "Default")
      (node (ref "U22") (pin "8") (pinfunction "8_8") (pintype "unspecified"))
    )
    (net (code "91") (name "unconnected-(U23-Pad7)") (class "Default")
      (node (ref "U23") (pin "7") (pinfunction "7_7") (pintype "unspecified"))
    )
    (net (code "92") (name "unconnected-(U23-Pad8)") (class "Default")
      (node (ref "U23") (pin "8") (pinfunction "8_8") (pintype "unspecified"))
    )
    (net (code "93") (name "unconnected-(U24-Pad7)") (class "Default")
      (node (ref "U24") (pin "7") (pinfunction "7_7") (pintype "unspecified"))
    )
    (net (code "94") (name "unconnected-(U24-Pad8)") (class "Default")
      (node (ref "U24") (pin "8") (pinfunction "8_8") (pintype "unspecified"))
    )
  )
)
